# base.net
KiCad netlist of a schematic drawn in EAGLE
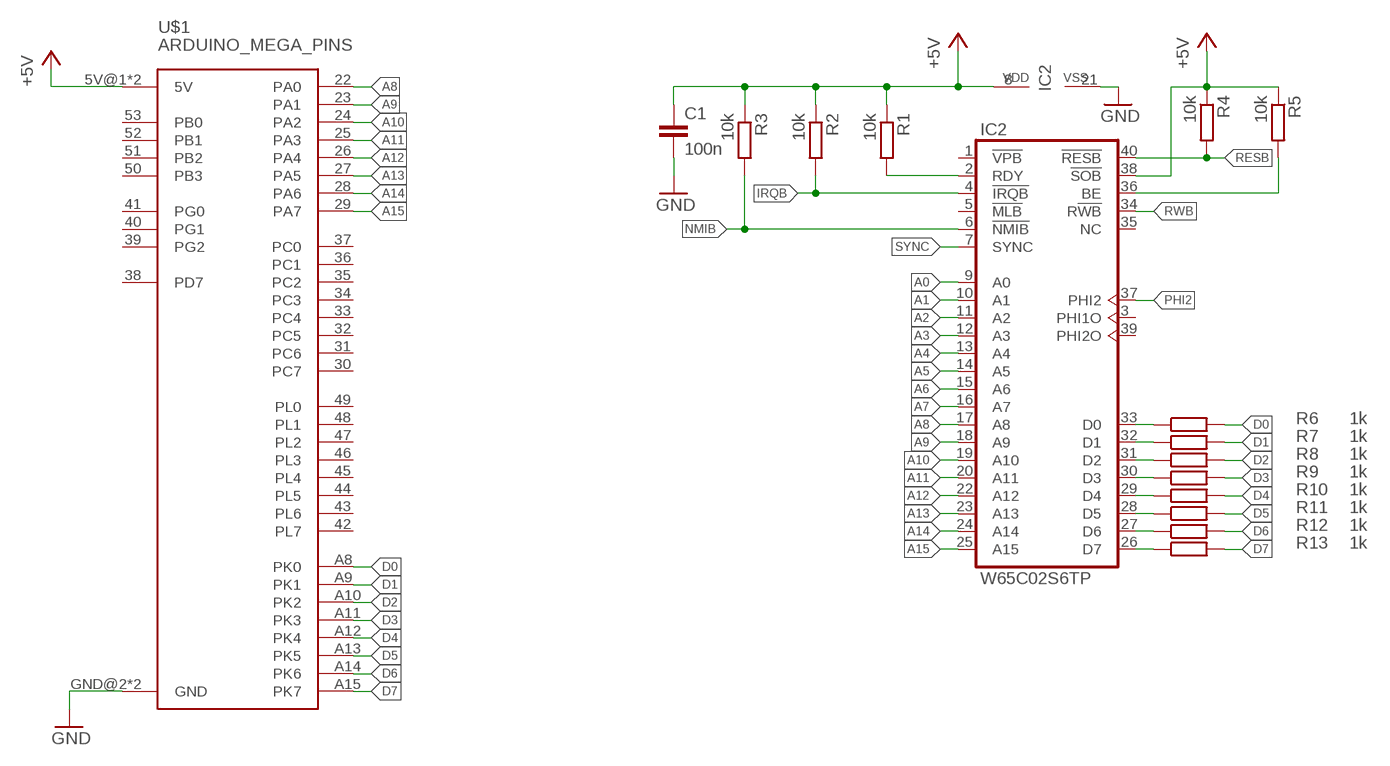
[diagram p0: schematic, sheet 1]

(export (version "E")
  (design (tool "Eeschema 10.0.6"))
  (components
    (comp (ref "C1")
      (value "100n")
      (footprint "eagle-import:C0805")
      (libsource (lib "eagle-import") (part "C-EUC0805"))
    )
    (comp (ref "IC2")
      (value "W65C02S6TP")
      (footprint "eagle-import:DIL40")
      (libsource (lib "eagle-import") (part "W65C02SP6T"))
    )
    (comp (ref "R1")
      (value "10k")
      (footprint "eagle-import:R0805")
      (libsource (lib "eagle-import") (part "R-EU_R0805"))
    )
    (comp (ref "R2")
      (value "10k")
      (footprint "eagle-import:R0805")
      (libsource (lib "eagle-import") (part "R-EU_R0805"))
    )
    (comp (ref "R3")
      (value "10k")
      (footprint "eagle-import:R0805")
      (libsource (lib "eagle-import") (part "R-EU_R0805"))
    )
    (comp (ref "R4")
      (value "10k")
      (footprint "eagle-import:R0805")
      (libsource (lib "eagle-import") (part "R-EU_R0805"))
    )
    (comp (ref "R5")
      (value "10k")
      (footprint "eagle-import:R0805")
      (libsource (lib "eagle-import") (part "R-EU_R0805"))
    )
    (comp (ref "R6")
      (value "1k")
      (footprint "eagle-import:R0805")
      (libsource (lib "eagle-import") (part "R-EU_R0805"))
    )
    (comp (ref "R7")
      (value "1k")
      (footprint "eagle-import:R0805")
      (libsource (lib "eagle-import") (part "R-EU_R0805"))
    )
    (comp (ref "R8")
      (value "1k")
      (footprint "eagle-import:R0805")
      (libsource (lib "eagle-import") (part "R-EU_R0805"))
    )
    (comp (ref "R9")
      (value "1k")
      (footprint "eagle-import:R0805")
      (libsource (lib "eagle-import") (part "R-EU_R0805"))
    )
    (comp (ref "R10")
      (value "1k")
      (footprint "eagle-import:R0805")
      (libsource (lib "eagle-import") (part "R-EU_R0805"))
    )
    (comp (ref "R11")
      (value "1k")
      (footprint "eagle-import:R0805")
      (libsource (lib "eagle-import") (part "R-EU_R0805"))
    )
    (comp (ref "R12")
      (value "1k")
      (footprint "eagle-import:R0805")
      (libsource (lib "eagle-import") (part "R-EU_R0805"))
    )
    (comp (ref "R13")
      (value "1k")
      (footprint "eagle-import:R0805")
      (libsource (lib "eagle-import") (part "R-EU_R0805"))
    )
    (comp (ref "U$1")
      (value "ARDUINO_MEGA_PINS")
      (footprint "eagle-import:ARDUINO_MEGA_PINS")
      (libsource (lib "eagle-import") (part "ARDUINO_MEGA_PINS"))
    )
  )
  (nets
    (net (code "1") (name "+5V") (class "Default")
      (node (ref "C1") (pin "1") (pinfunction "1_1") (pintype "passive"))
      (node (ref "IC2") (pin "38") (pinfunction "~{SOB}_38") (pintype "input"))
      (node (ref "IC2") (pin "8") (pinfunction "VDD_8") (pintype "power_in"))
      (node (ref "R1") (pin "1") (pinfunction "1_1") (pintype "passive"))
      (node (ref "R2") (pin "1") (pinfunction "1_1") (pintype "passive"))
      (node (ref "R3") (pin "1") (pinfunction "1_1") (pintype "passive"))
      (node (ref "R4") (pin "1") (pinfunction "1_1") (pintype "passive"))
      (node (ref "R5") (pin "1") (pinfunction "1_1") (pintype "passive"))
      (node (ref "U$1") (pin "5V@1") (pinfunction "5V_5V@1") (pintype "bidirectional"))
      (node (ref "U$1") (pin "5V@2") (pinfunction "5V_5V@2") (pintype "bidirectional"))
    )
    (net (code "2") (name "A0") (class "Default")
      (node (ref "IC2") (pin "9") (pinfunction "A0_9") (pintype "output"))
    )
    (net (code "3") (name "A1") (class "Default")
      (node (ref "IC2") (pin "10") (pinfunction "A1_10") (pintype "output"))
    )
    (net (code "4") (name "A2") (class "Default")
      (node (ref "IC2") (pin "11") (pinfunction "A2_11") (pintype "output"))
    )
    (net (code "5") (name "A3") (class "Default")
      (node (ref "IC2") (pin "12") (pinfunction "A3_12") (pintype "output"))
    )
    (net (code "6") (name "A4") (class "Default")
      (node (ref "IC2") (pin "13") (pinfunction "A4_13") (pintype "output"))
    )
    (net (code "7") (name "A5") (class "Default")
      (node (ref "IC2") (pin "14") (pinfunction "A5_14") (pintype "output"))
    )
    (net (code "8") (name "A6") (class "Default")
      (node (ref "IC2") (pin "15") (pinfunction "A6_15") (pintype "output"))
    )
    (net (code "9") (name "A7") (class "Default")
      (node (ref "IC2") (pin "16") (pinfunction "A7_16") (pintype "output"))
    )
    (net (code "10") (name "A8") (class "Default")
      (node (ref "IC2") (pin "17") (pinfunction "A8_17") (pintype "output"))
      (node (ref "U$1") (pin "22") (pinfunction "PA0_22") (pintype "bidirectional"))
    )
    (net (code "11") (name "A9") (class "Default")
      (node (ref "IC2") (pin "18") (pinfunction "A9_18") (pintype "output"))
      (node (ref "U$1") (pin "23") (pinfunction "PA1_23") (pintype "bidirectional"))
    )
    (net (code "12") (name "A10") (class "Default")
      (node (ref "IC2") (pin "19") (pinfunction "A10_19") (pintype "output"))
      (node (ref "U$1") (pin "24") (pinfunction "PA2_24") (pintype "bidirectional"))
    )
    (net (code "13") (name "A11") (class "Default")
      (node (ref "IC2") (pin "20") (pinfunction "A11_20") (pintype "output"))
      (node (ref "U$1") (pin "25") (pinfunction "PA3_25") (pintype "bidirectional"))
    )
    (net (code "14") (name "A12") (class "Default")
      (node (ref "IC2") (pin "22") (pinfunction "A12_22") (pintype "output"))
      (node (ref "U$1") (pin "26") (pinfunction "PA4_26") (pintype "bidirectional"))
    )
    (net (code "15") (name "A13") (class "Default")
      (node (ref "IC2") (pin "23") (pinfunction "A13_23") (pintype "output"))
      (node (ref "U$1") (pin "27") (pinfunction "PA5_27") (pintype "bidirectional"))
    )
    (net (code "16") (name "A14") (class "Default")
      (node (ref "IC2") (pin "24") (pinfunction "A14_24") (pintype "output"))
      (node (ref "U$1") (pin "28") (pinfunction "PA6_28") (pintype "bidirectional"))
    )
    (net (code "17") (name "A15") (class "Default")
      (node (ref "IC2") (pin "25") (pinfunction "A15_25") (pintype "output"))
      (node (ref "U$1") (pin "29") (pinfunction "PA7_29") (pintype "bidirectional"))
    )
    (net (code "18") (name "D0") (class "Default")
      (node (ref "R6") (pin "2") (pinfunction "2_2") (pintype "passive"))
      (node (ref "U$1") (pin "A8") (pinfunction "PK0_A8") (pintype "bidirectional"))
    )
    (net (code "19") (name "D1") (class "Default")
      (node (ref "R7") (pin "2") (pinfunction "2_2") (pintype "passive"))
      (node (ref "U$1") (pin "A9") (pinfunction "PK1_A9") (pintype "bidirectional"))
    )
    (net (code "20") (name "D2") (class "Default")
      (node (ref "R8") (pin "2") (pinfunction "2_2") (pintype "passive"))
      (node (ref "U$1") (pin "A10") (pinfunction "PK2_A10") (pintype "bidirectional"))
    )
    (net (code "21") (name "D3") (class "Default")
      (node (ref "R9") (pin "2") (pinfunction "2_2") (pintype "passive"))
      (node (ref "U$1") (pin "A11") (pinfunction "PK3_A11") (pintype "bidirectional"))
    )
    (net (code "22") (name "D4") (class "Default")
      (node (ref "R10") (pin "2") (pinfunction "2_2") (pintype "passive"))
      (node (ref "U$1") (pin "A12") (pinfunction "PK4_A12") (pintype "bidirectional"))
    )
    (net (code "23") (name "D5") (class "Default")
      (node (ref "R11") (pin "2") (pinfunction "2_2") (pintype "passive"))
      (node (ref "U$1") (pin "A13") (pinfunction "PK5_A13") (pintype "bidirectional"))
    )
    (net (code "24") (name "D6") (class "Default")
      (node (ref "R12") (pin "2") (pinfunction "2_2") (pintype "passive"))
      (node (ref "U$1") (pin "A14") (pinfunction "PK6_A14") (pintype "bidirectional"))
    )
    (net (code "25") (name "D7") (class "Default")
      (node (ref "R13") (pin "2") (pinfunction "2_2") (pintype "passive"))
      (node (ref "U$1") (pin "A15") (pinfunction "PK7_A15") (pintype "bidirectional"))
    )
    (net (code "26") (name "GND") (class "Default")
      (node (ref "C1") (pin "2") (pinfunction "2_2") (pintype "passive"))
      (node (ref "IC2") (pin "21") (pinfunction "VSS_21") (pintype "power_in"))
      (node (ref "U$1") (pin "GND@2") (pinfunction "GND_GND@2") (pintype "bidirectional"))
      (node (ref "U$1") (pin "GND@3") (pinfunction "GND_GND@3") (pintype "bidirectional"))
    )
    (net (code "27") (name "IRQB") (class "Default")
      (node (ref "IC2") (pin "4") (pinfunction "~{IRQB}_4") (pintype "input"))
      (node (ref "R2") (pin "2") (pinfunction "2_2") (pintype "passive"))
    )
    (net (code "28") (name "NMIB") (class "Default")
      (node (ref "IC2") (pin "6") (pinfunction "~{NMIB}_6") (pintype "input"))
      (node (ref "R3") (pin "2") (pinfunction "2_2") (pintype "passive"))
    )
    (net (code "29") (name "Net-(IC2A-BE)") (class "Default")
      (node (ref "IC2") (pin "36") (pinfunction "BE_36") (pintype "input"))
      (node (ref "R5") (pin "2") (pinfunction "2_2") (pintype "passive"))
    )
    (net (code "30") (name "Net-(IC2A-D0)") (class "Default")
      (node (ref "IC2") (pin "33") (pinfunction "D0_33") (pintype "bidirectional"))
      (node (ref "R6") (pin "1") (pinfunction "1_1") (pintype "passive"))
    )
    (net (code "31") (name "Net-(IC2A-D1)") (class "Default")
      (node (ref "IC2") (pin "32") (pinfunction "D1_32") (pintype "bidirectional"))
      (node (ref "R7") (pin "1") (pinfunction "1_1") (pintype "passive"))
    )
    (net (code "32") (name "Net-(IC2A-D2)") (class "Default")
      (node (ref "IC2") (pin "31") (pinfunction "D2_31") (pintype "bidirectional"))
      (node (ref "R8") (pin "1") (pinfunction "1_1") (pintype "passive"))
    )
    (net (code "33") (name "Net-(IC2A-D3)") (class "Default")
      (node (ref "IC2") (pin "30") (pinfunction "D3_30") (pintype "bidirectional"))
      (node (ref "R9") (pin "1") (pinfunction "1_1") (pintype "passive"))
    )
    (net (code "34") (name "Net-(IC2A-D4)") (class "Default")
      (node (ref "IC2") (pin "29") (pinfunction "D4_29") (pintype "bidirectional"))
      (node (ref "R10") (pin "1") (pinfunction "1_1") (pintype "passive"))
    )
    (net (code "35") (name "Net-(IC2A-D5)") (class "Default")
      (node (ref "IC2") (pin "28") (pinfunction "D5_28") (pintype "bidirectional"))
      (node (ref "R11") (pin "1") (pinfunction "1_1") (pintype "passive"))
    )
    (net (code "36") (name "Net-(IC2A-D6)") (class "Default")
      (node (ref "IC2") (pin "27") (pinfunction "D6_27") (pintype "bidirectional"))
      (node (ref "R12") (pin "1") (pinfunction "1_1") (pintype "passive"))
    )
    (net (code "37") (name "Net-(IC2A-D7)") (class "Default")
      (node (ref "IC2") (pin "26") (pinfunction "D7_26") (pintype "bidirectional"))
      (node (ref "R13") (pin "1") (pinfunction "1_1") (pintype "passive"))
    )
    (net (code "38") (name "Net-(IC2A-RDY)") (class "Default")
      (node (ref "IC2") (pin "2") (pinfunction "RDY_2") (pintype "input"))
      (node (ref "R1") (pin "2") (pinfunction "2_2") (pintype "passive"))
    )
    (net (code "39") (name "PHI2") (class "Default")
      (node (ref "IC2") (pin "37") (pinfunction "PHI2_37") (pintype "input"))
    )
    (net (code "40") (name "RESB") (class "Default")
      (node (ref "IC2") (pin "40") (pinfunction "~{RESB}_40") (pintype "input"))
      (node (ref "R4") (pin "2") (pinfunction "2_2") (pintype "passive"))
    )
    (net (code "41") (name "RWB") (class "Default")
      (node (ref "IC2") (pin "34") (pinfunction "R~{WB}_34") (pintype "output"))
    )
    (net (code "42") (name "SYNC") (class "Default")
      (node (ref "IC2") (pin "7") (pinfunction "SYNC_7") (pintype "output"))
    )
    (net (code "43") (name "unconnected-(IC2A-NC-Pad35)") (class "Default")
      (node (ref "IC2") (pin "35") (pinfunction "NC_35") (pintype "no_connect"))
    )
    (net (code "44") (name "unconnected-(IC2A-PHI1O-Pad3)") (class "Default")
      (node (ref "IC2") (pin "3") (pinfunction "PHI1O_3") (pintype "output"))
    )
    (net (code "45") (name "unconnected-(IC2A-PHI2O-Pad39)") (class "Default")
      (node (ref "IC2") (pin "39") (pinfunction "PHI2O_39") (pintype "output"))
    )
    (net (code "46") (name "unconnected-(IC2A-~{MLB}-Pad5)") (class "Default")
      (node (ref "IC2") (pin "5") (pinfunction "~{MLB}_5") (pintype "output"))
    )
    (net (code "47") (name "unconnected-(IC2A-~{VPB}-Pad1)") (class "Default")
      (node (ref "IC2") (pin "1") (pinfunction "~{VPB}_1") (pintype "output"))
    )
    (net (code "48") (name "unconnected-(U$1-PB0-Pad53)") (class "Default")
      (node (ref "U$1") (pin "53") (pinfunction "PB0_53") (pintype "bidirectional"))
    )
    (net (code "49") (name "unconnected-(U$1-PB1-Pad52)") (class "Default")
      (node (ref "U$1") (pin "52") (pinfunction "PB1_52") (pintype "bidirectional"))
    )
    (net (code "50") (name "unconnected-(U$1-PB2-Pad51)") (class "Default")
      (node (ref "U$1") (pin "51") (pinfunction "PB2_51") (pintype "bidirectional"))
    )
    (net (code "51") (name "unconnected-(U$1-PB3-Pad50)") (class "Default")
      (node (ref "U$1") (pin "50") (pinfunction "PB3_50") (pintype "bidirectional"))
    )
    (net (code "52") (name "unconnected-(U$1-PC0-Pad37)") (class "Default")
      (node (ref "U$1") (pin "37") (pinfunction "PC0_37") (pintype "bidirectional"))
    )
    (net (code "53") (name "unconnected-(U$1-PC1-Pad36)") (class "Default")
      (node (ref "U$1") (pin "36") (pinfunction "PC1_36") (pintype "bidirectional"))
    )
    (net (code "54") (name "unconnected-(U$1-PC2-Pad35)") (class "Default")
      (node (ref "U$1") (pin "35") (pinfunction "PC2_35") (pintype "bidirectional"))
    )
    (net (code "55") (name "unconnected-(U$1-PC3-Pad34)") (class "Default")
      (node (ref "U$1") (pin "34") (pinfunction "PC3_34") (pintype "bidirectional"))
    )
    (net (code "56") (name "unconnected-(U$1-PC4-Pad33)") (class "Default")
      (node (ref "U$1") (pin "33") (pinfunction "PC4_33") (pintype "bidirectional"))
    )
    (net (code "57") (name "unconnected-(U$1-PC5-Pad32)") (class "Default")
      (node (ref "U$1") (pin "32") (pinfunction "PC5_32") (pintype "bidirectional"))
    )
    (net (code "58") (name "unconnected-(U$1-PC6-Pad31)") (class "Default")
      (node (ref "U$1") (pin "31") (pinfunction "PC6_31") (pintype "bidirectional"))
    )
    (net (code "59") (name "unconnected-(U$1-PC7-Pad30)") (class "Default")
      (node (ref "U$1") (pin "30") (pinfunction "PC7_30") (pintype "bidirectional"))
    )
    (net (code "60") (name "unconnected-(U$1-PD7-Pad38)") (class "Default")
      (node (ref "U$1") (pin "38") (pinfunction "PD7_38") (pintype "bidirectional"))
    )
    (net (code "61") (name "unconnected-(U$1-PG0-Pad41)") (class "Default")
      (node (ref "U$1") (pin "41") (pinfunction "PG0_41") (pintype "bidirectional"))
    )
    (net (code "62") (name "unconnected-(U$1-PG1-Pad40)") (class "Default")
      (node (ref "U$1") (pin "40") (pinfunction "PG1_40") (pintype "bidirectional"))
    )
    (net (code "63") (name "unconnected-(U$1-PG2-Pad39)") (class "Default")
      (node (ref "U$1") (pin "39") (pinfunction "PG2_39") (pintype "bidirectional"))
    )
    (net (code "64") (name "unconnected-(U$1-PL0-Pad49)") (class "Default")
      (node (ref "U$1") (pin "49") (pinfunction "PL0_49") (pintype "bidirectional"))
    )
    (net (code "65") (name "unconnected-(U$1-PL1-Pad48)") (class "Default")
      (node (ref "U$1") (pin "48") (pinfunction "PL1_48") (pintype "bidirectional"))
    )
    (net (code "66") (name "unconnected-(U$1-PL2-Pad47)") (class "Default")
      (node (ref "U$1") (pin "47") (pinfunction "PL2_47") (pintype "bidirectional"))
    )
    (net (code "67") (name "unconnected-(U$1-PL3-Pad46)") (class "Default")
      (node (ref "U$1") (pin "46") (pinfunction "PL3_46") (pintype "bidirectional"))
    )
    (net (code "68") (name "unconnected-(U$1-PL4-Pad45)") (class "Default")
      (node (ref "U$1") (pin "45") (pinfunction "PL4_45") (pintype "bidirectional"))
    )
    (net (code "69") (name "unconnected-(U$1-PL5-Pad44)") (class "Default")
      (node (ref "U$1") (pin "44") (pinfunction "PL5_44") (pintype "bidirectional"))
    )
    (net (code "70") (name "unconnected-(U$1-PL6-Pad43)") (class "Default")
      (node (ref "U$1") (pin "43") (pinfunction "PL6_43") (pintype "bidirectional"))
    )
    (net (code "71") (name "unconnected-(U$1-PL7-Pad42)") (class "Default")
      (node (ref "U$1") (pin "42") (pinfunction "PL7_42") (pintype "bidirectional"))
    )
  )
)
